# IO_Bottom.net
KiCad netlist of a schematic drawn in EAGLE
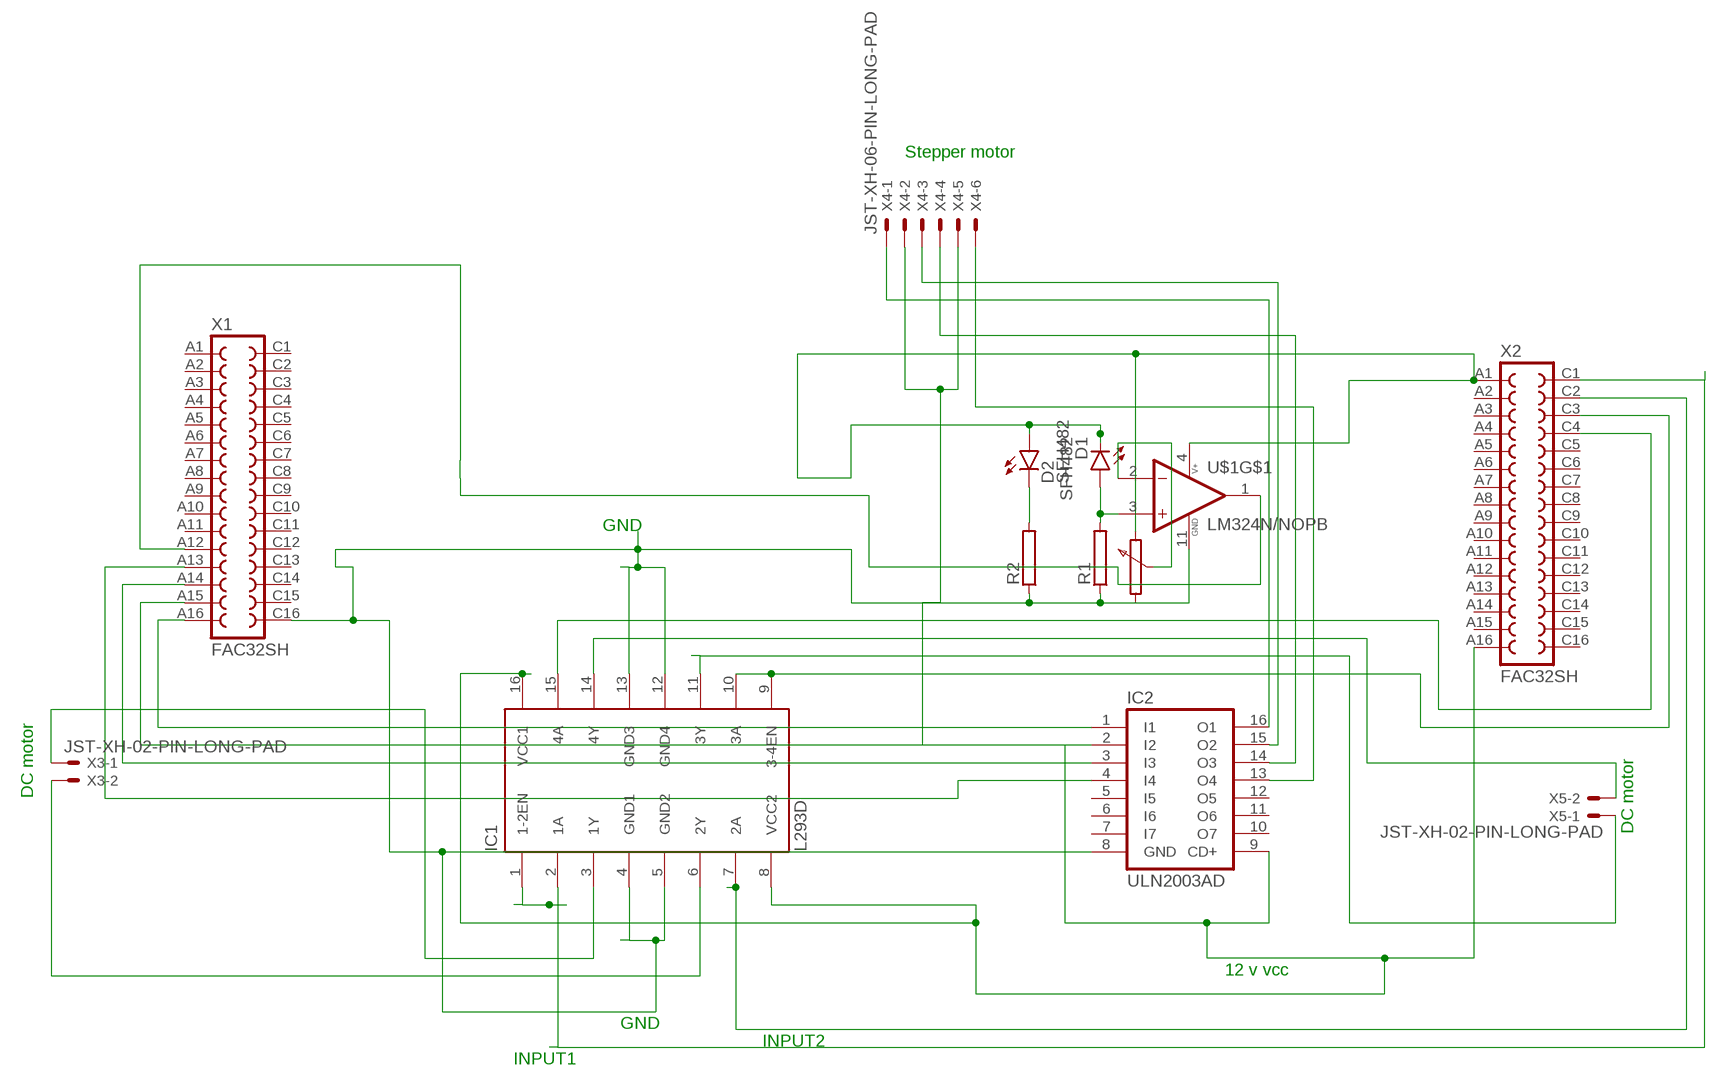
[diagram p0: schematic, sheet 1]

(export (version "E")
  (design (tool "Eeschema 10.0.6"))
  (components
    (comp (ref "D1")
      (value "SFH482")
      (footprint "eagle-import:SFH482")
      (libsource (lib "eagle-import") (part "SFH482"))
    )
    (comp (ref "D2")
      (value "SFH482")
      (footprint "eagle-import:SFH482")
      (libsource (lib "eagle-import") (part "SFH482"))
    )
    (comp (ref "IC1")
      (value "L293D")
      (footprint "eagle-import:DIL16")
      (libsource (lib "eagle-import") (part "L293D"))
    )
    (comp (ref "IC2")
      (value "ULN2003AD")
      (footprint "eagle-import:SO16")
      (libsource (lib "eagle-import") (part "ULN2003AD"))
    )
    (comp (ref "R1")
      (value "RMG100-H")
      (footprint "eagle-import:TO-247-2H")
      (libsource (lib "eagle-import") (part "RMG100-H"))
    )
    (comp (ref "R2")
      (value "RMG100-H")
      (footprint "eagle-import:TO-247-2H")
      (libsource (lib "eagle-import") (part "RMG100-H"))
    )
    (comp (ref "U$1")
      (value "LM324N/NOPB")
      (footprint "eagle-import:DIP825W47P254L1917H533Q14")
      (fields (field (name "MF") "Texas Instruments") (field (name "MP") "LM324N"))
      (libsource (lib "eagle-import") (part "LM324N/NOPB"))
    )
    (comp (ref "X1")
      (value "FAC32SH")
      (footprint "eagle-import:FAC32SH")
      (libsource (lib "eagle-import") (part "FAC32SH"))
    )
    (comp (ref "X2")
      (value "FAC32SH")
      (footprint "eagle-import:FAC32SH")
      (libsource (lib "eagle-import") (part "FAC32SH"))
    )
    (comp (ref "X3")
      (value "JST-XH-02-PIN-LONG-PAD")
      (footprint "eagle-import:JST-XH-02-PACKAGE-LONG-PAD")
      (libsource (lib "eagle-import") (part "JST-XH-02-PIN-LONG-PAD"))
    )
    (comp (ref "X4")
      (value "JST-XH-06-PIN-LONG-PAD")
      (footprint "eagle-import:JST-XH-06-PACKAGE-LONG-PAD")
      (libsource (lib "eagle-import") (part "JST-XH-06-PIN-LONG-PAD"))
    )
    (comp (ref "X5")
      (value "JST-XH-02-PIN-LONG-PAD")
      (footprint "eagle-import:JST-XH-02-PACKAGE-LONG-PAD")
      (libsource (lib "eagle-import") (part "JST-XH-02-PIN-LONG-PAD"))
    )
  )
  (nets
    (net (code "1") (name "Net-(D1-C)") (class "Default")
      (node (ref "D1") (pin "K") (pinfunction "C_K") (pintype "passive"))
      (node (ref "D2") (pin "A") (pinfunction "A_A") (pintype "passive"))
      (node (ref "U$1") (pin "4") (pinfunction "V+_4") (pintype "power_in"))
      (node (ref "X2") (pin "A1") (pinfunction "A1_A1") (pintype "passive"))
    )
    (net (code "2") (name "Net-(D2-C)") (class "Default")
      (node (ref "D2") (pin "K") (pinfunction "C_K") (pintype "passive"))
      (node (ref "R2") (pin "2") (pinfunction "2_2") (pintype "passive"))
    )
    (net (code "3") (name "Net-(IC1-1A)") (class "Default")
      (node (ref "IC1") (pin "2") (pinfunction "1A_2") (pintype "input"))
      (node (ref "X2") (pin "C1") (pinfunction "C1_C1") (pintype "passive"))
    )
    (net (code "4") (name "Net-(IC1-1Y)") (class "Default")
      (node (ref "IC1") (pin "3") (pinfunction "1Y_3") (pintype "output"))
      (node (ref "X3") (pin "1") (pinfunction "S_1") (pintype "passive"))
    )
    (net (code "5") (name "Net-(IC1-2A)") (class "Default")
      (node (ref "IC1") (pin "7") (pinfunction "2A_7") (pintype "input"))
      (node (ref "X2") (pin "C2") (pinfunction "C2_C2") (pintype "passive"))
    )
    (net (code "6") (name "Net-(IC1-2Y)") (class "Default")
      (node (ref "IC1") (pin "6") (pinfunction "2Y_6") (pintype "output"))
      (node (ref "X3") (pin "2") (pinfunction "S_2") (pintype "passive"))
    )
    (net (code "7") (name "Net-(IC1-3-4EN)") (class "Default")
      (node (ref "IC1") (pin "10") (pinfunction "3A_10") (pintype "input"))
      (node (ref "IC1") (pin "9") (pinfunction "3-4EN_9") (pintype "input"))
      (node (ref "X2") (pin "C3") (pinfunction "C3_C3") (pintype "passive"))
    )
    (net (code "8") (name "Net-(IC1-3Y)") (class "Default")
      (node (ref "IC1") (pin "11") (pinfunction "3Y_11") (pintype "output"))
      (node (ref "X5") (pin "1") (pinfunction "S_1") (pintype "passive"))
    )
    (net (code "9") (name "Net-(IC1-4A)") (class "Default")
      (node (ref "IC1") (pin "15") (pinfunction "4A_15") (pintype "input"))
      (node (ref "X2") (pin "C4") (pinfunction "C4_C4") (pintype "passive"))
    )
    (net (code "10") (name "Net-(IC1-4Y)") (class "Default")
      (node (ref "IC1") (pin "14") (pinfunction "4Y_14") (pintype "output"))
      (node (ref "X5") (pin "2") (pinfunction "S_2") (pintype "passive"))
    )
    (net (code "11") (name "Net-(IC1-GND1)") (class "Default")
      (node (ref "IC1") (pin "12") (pinfunction "GND4_12") (pintype "power_in"))
      (node (ref "IC1") (pin "13") (pinfunction "GND3_13") (pintype "power_in"))
      (node (ref "IC1") (pin "4") (pinfunction "GND1_4") (pintype "power_in"))
      (node (ref "IC1") (pin "5") (pinfunction "GND2_5") (pintype "power_in"))
      (node (ref "IC2") (pin "8") (pinfunction "GND_8") (pintype "power_in"))
      (node (ref "R1") (pin "1") (pinfunction "1_1") (pintype "passive"))
      (node (ref "R2") (pin "1") (pinfunction "1_1") (pintype "passive"))
      (node (ref "U$1") (pin "11") (pinfunction "GND_11") (pintype "power_in"))
      (node (ref "X1") (pin "C16") (pinfunction "C16_C16") (pintype "passive"))
    )
    (net (code "12") (name "Net-(IC1-VCC1)") (class "Default")
      (node (ref "IC1") (pin "16") (pinfunction "VCC1_16") (pintype "power_in"))
      (node (ref "IC1") (pin "8") (pinfunction "VCC2_8") (pintype "power_in"))
      (node (ref "IC2") (pin "9") (pinfunction "CD+_9") (pintype "passive"))
      (node (ref "X2") (pin "A16") (pinfunction "A16_A16") (pintype "passive"))
      (node (ref "X4") (pin "2") (pinfunction "S_2") (pintype "passive"))
      (node (ref "X4") (pin "5") (pinfunction "S_5") (pintype "passive"))
    )
    (net (code "13") (name "Net-(IC2-I1)") (class "Default")
      (node (ref "IC2") (pin "1") (pinfunction "I1_1") (pintype "input"))
      (node (ref "X1") (pin "A16") (pinfunction "A16_A16") (pintype "passive"))
    )
    (net (code "14") (name "Net-(IC2-I2)") (class "Default")
      (node (ref "IC2") (pin "2") (pinfunction "I2_2") (pintype "input"))
      (node (ref "X1") (pin "A15") (pinfunction "A15_A15") (pintype "passive"))
    )
    (net (code "15") (name "Net-(IC2-I3)") (class "Default")
      (node (ref "IC2") (pin "3") (pinfunction "I3_3") (pintype "input"))
      (node (ref "X1") (pin "A14") (pinfunction "A14_A14") (pintype "passive"))
    )
    (net (code "16") (name "Net-(IC2-I4)") (class "Default")
      (node (ref "IC2") (pin "4") (pinfunction "I4_4") (pintype "input"))
      (node (ref "X1") (pin "A13") (pinfunction "A13_A13") (pintype "passive"))
    )
    (net (code "17") (name "Net-(IC2-O1)") (class "Default")
      (node (ref "IC2") (pin "16") (pinfunction "O1_16") (pintype "open_collector"))
      (node (ref "X4") (pin "1") (pinfunction "S_1") (pintype "passive"))
    )
    (net (code "18") (name "Net-(IC2-O2)") (class "Default")
      (node (ref "IC2") (pin "15") (pinfunction "O2_15") (pintype "open_collector"))
      (node (ref "X4") (pin "3") (pinfunction "S_3") (pintype "passive"))
    )
    (net (code "19") (name "Net-(IC2-O3)") (class "Default")
      (node (ref "IC2") (pin "14") (pinfunction "O3_14") (pintype "open_collector"))
      (node (ref "X4") (pin "4") (pinfunction "S_4") (pintype "passive"))
    )
    (net (code "20") (name "Net-(IC2-O4)") (class "Default")
      (node (ref "IC2") (pin "13") (pinfunction "O4_13") (pintype "open_collector"))
      (node (ref "X4") (pin "6") (pinfunction "S_6") (pintype "passive"))
    )
    (net (code "21") (name "Net-(U$1A-1IN+)") (class "Default")
      (node (ref "D1") (pin "A") (pinfunction "A_A") (pintype "passive"))
      (node (ref "R1") (pin "2") (pinfunction "2_2") (pintype "passive"))
      (node (ref "U$1") (pin "3") (pinfunction "1IN+_3") (pintype "input"))
    )
    (net (code "22") (name "Net-(U$1A-1OUT)") (class "Default")
      (node (ref "U$1") (pin "1") (pinfunction "1OUT_1") (pintype "output"))
      (node (ref "X1") (pin "A12") (pinfunction "A12_A12") (pintype "passive"))
    )
    (net (code "23") (name "unconnected-(IC1-1-2EN-Pad1)") (class "Default")
      (node (ref "IC1") (pin "1") (pinfunction "1-2EN_1") (pintype "input"))
    )
    (net (code "24") (name "unconnected-(IC2-I5-Pad5)") (class "Default")
      (node (ref "IC2") (pin "5") (pinfunction "I5_5") (pintype "input"))
    )
    (net (code "25") (name "unconnected-(IC2-I6-Pad6)") (class "Default")
      (node (ref "IC2") (pin "6") (pinfunction "I6_6") (pintype "input"))
    )
    (net (code "26") (name "unconnected-(IC2-I7-Pad7)") (class "Default")
      (node (ref "IC2") (pin "7") (pinfunction "I7_7") (pintype "input"))
    )
    (net (code "27") (name "unconnected-(IC2-O5-Pad12)") (class "Default")
      (node (ref "IC2") (pin "12") (pinfunction "O5_12") (pintype "open_collector"))
    )
    (net (code "28") (name "unconnected-(IC2-O6-Pad11)") (class "Default")
      (node (ref "IC2") (pin "11") (pinfunction "O6_11") (pintype "open_collector"))
    )
    (net (code "29") (name "unconnected-(IC2-O7-Pad10)") (class "Default")
      (node (ref "IC2") (pin "10") (pinfunction "O7_10") (pintype "open_collector"))
    )
    (net (code "30") (name "unconnected-(U$1A-1IN--Pad2)") (class "Default")
      (node (ref "U$1") (pin "2") (pinfunction "1IN-_2") (pintype "input"))
    )
    (net (code "31") (name "unconnected-(X1-PadA1)") (class "Default")
      (node (ref "X1") (pin "A1") (pinfunction "A1_A1") (pintype "passive"))
    )
    (net (code "32") (name "unconnected-(X1-PadA2)") (class "Default")
      (node (ref "X1") (pin "A2") (pinfunction "A2_A2") (pintype "passive"))
    )
    (net (code "33") (name "unconnected-(X1-PadA3)") (class "Default")
      (node (ref "X1") (pin "A3") (pinfunction "A3_A3") (pintype "passive"))
    )
    (net (code "34") (name "unconnected-(X1-PadA4)") (class "Default")
      (node (ref "X1") (pin "A4") (pinfunction "A4_A4") (pintype "passive"))
    )
    (net (code "35") (name "unconnected-(X1-PadA5)") (class "Default")
      (node (ref "X1") (pin "A5") (pinfunction "A5_A5") (pintype "passive"))
    )
    (net (code "36") (name "unconnected-(X1-PadA6)") (class "Default")
      (node (ref "X1") (pin "A6") (pinfunction "A6_A6") (pintype "passive"))
    )
    (net (code "37") (name "unconnected-(X1-PadA7)") (class "Default")
      (node (ref "X1") (pin "A7") (pinfunction "A7_A7") (pintype "passive"))
    )
    (net (code "38") (name "unconnected-(X1-PadA8)") (class "Default")
      (node (ref "X1") (pin "A8") (pinfunction "A8_A8") (pintype "passive"))
    )
    (net (code "39") (name "unconnected-(X1-PadA9)") (class "Default")
      (node (ref "X1") (pin "A9") (pinfunction "A9_A9") (pintype "passive"))
    )
    (net (code "40") (name "unconnected-(X1-PadA10)") (class "Default")
      (node (ref "X1") (pin "A10") (pinfunction "A10_A10") (pintype "passive"))
    )
    (net (code "41") (name "unconnected-(X1-PadA11)") (class "Default")
      (node (ref "X1") (pin "A11") (pinfunction "A11_A11") (pintype "passive"))
    )
    (net (code "42") (name "unconnected-(X1-PadC1)") (class "Default")
      (node (ref "X1") (pin "C1") (pinfunction "C1_C1") (pintype "passive"))
    )
    (net (code "43") (name "unconnected-(X1-PadC2)") (class "Default")
      (node (ref "X1") (pin "C2") (pinfunction "C2_C2") (pintype "passive"))
    )
    (net (code "44") (name "unconnected-(X1-PadC3)") (class "Default")
      (node (ref "X1") (pin "C3") (pinfunction "C3_C3") (pintype "passive"))
    )
    (net (code "45") (name "unconnected-(X1-PadC4)") (class "Default")
      (node (ref "X1") (pin "C4") (pinfunction "C4_C4") (pintype "passive"))
    )
    (net (code "46") (name "unconnected-(X1-PadC5)") (class "Default")
      (node (ref "X1") (pin "C5") (pinfunction "C5_C5") (pintype "passive"))
    )
    (net (code "47") (name "unconnected-(X1-PadC6)") (class "Default")
      (node (ref "X1") (pin "C6") (pinfunction "C6_C6") (pintype "passive"))
    )
    (net (code "48") (name "unconnected-(X1-PadC7)") (class "Default")
      (node (ref "X1") (pin "C7") (pinfunction "C7_C7") (pintype "passive"))
    )
    (net (code "49") (name "unconnected-(X1-PadC8)") (class "Default")
      (node (ref "X1") (pin "C8") (pinfunction "C8_C8") (pintype "passive"))
    )
    (net (code "50") (name "unconnected-(X1-PadC9)") (class "Default")
      (node (ref "X1") (pin "C9") (pinfunction "C9_C9") (pintype "passive"))
    )
    (net (code "51") (name "unconnected-(X1-PadC10)") (class "Default")
      (node (ref "X1") (pin "C10") (pinfunction "C10_C10") (pintype "passive"))
    )
    (net (code "52") (name "unconnected-(X1-PadC11)") (class "Default")
      (node (ref "X1") (pin "C11") (pinfunction "C11_C11") (pintype "passive"))
    )
    (net (code "53") (name "unconnected-(X1-PadC12)") (class "Default")
      (node (ref "X1") (pin "C12") (pinfunction "C12_C12") (pintype "passive"))
    )
    (net (code "54") (name "unconnected-(X1-PadC13)") (class "Default")
      (node (ref "X1") (pin "C13") (pinfunction "C13_C13") (pintype "passive"))
    )
    (net (code "55") (name "unconnected-(X1-PadC14)") (class "Default")
      (node (ref "X1") (pin "C14") (pinfunction "C14_C14") (pintype "passive"))
    )
    (net (code "56") (name "unconnected-(X1-PadC15)") (class "Default")
      (node (ref "X1") (pin "C15") (pinfunction "C15_C15") (pintype "passive"))
    )
    (net (code "57") (name "unconnected-(X2-PadA2)") (class "Default")
      (node (ref "X2") (pin "A2") (pinfunction "A2_A2") (pintype "passive"))
    )
    (net (code "58") (name "unconnected-(X2-PadA3)") (class "Default")
      (node (ref "X2") (pin "A3") (pinfunction "A3_A3") (pintype "passive"))
    )
    (net (code "59") (name "unconnected-(X2-PadA4)") (class "Default")
      (node (ref "X2") (pin "A4") (pinfunction "A4_A4") (pintype "passive"))
    )
    (net (code "60") (name "unconnected-(X2-PadA5)") (class "Default")
      (node (ref "X2") (pin "A5") (pinfunction "A5_A5") (pintype "passive"))
    )
    (net (code "61") (name "unconnected-(X2-PadA6)") (class "Default")
      (node (ref "X2") (pin "A6") (pinfunction "A6_A6") (pintype "passive"))
    )
    (net (code "62") (name "unconnected-(X2-PadA7)") (class "Default")
      (node (ref "X2") (pin "A7") (pinfunction "A7_A7") (pintype "passive"))
    )
    (net (code "63") (name "unconnected-(X2-PadA8)") (class "Default")
      (node (ref "X2") (pin "A8") (pinfunction "A8_A8") (pintype "passive"))
    )
    (net (code "64") (name "unconnected-(X2-PadA9)") (class "Default")
      (node (ref "X2") (pin "A9") (pinfunction "A9_A9") (pintype "passive"))
    )
    (net (code "65") (name "unconnected-(X2-PadA10)") (class "Default")
      (node (ref "X2") (pin "A10") (pinfunction "A10_A10") (pintype "passive"))
    )
    (net (code "66") (name "unconnected-(X2-PadA11)") (class "Default")
      (node (ref "X2") (pin "A11") (pinfunction "A11_A11") (pintype "passive"))
    )
    (net (code "67") (name "unconnected-(X2-PadA12)") (class "Default")
      (node (ref "X2") (pin "A12") (pinfunction "A12_A12") (pintype "passive"))
    )
    (net (code "68") (name "unconnected-(X2-PadA13)") (class "Default")
      (node (ref "X2") (pin "A13") (pinfunction "A13_A13") (pintype "passive"))
    )
    (net (code "69") (name "unconnected-(X2-PadA14)") (class "Default")
      (node (ref "X2") (pin "A14") (pinfunction "A14_A14") (pintype "passive"))
    )
    (net (code "70") (name "unconnected-(X2-PadA15)") (class "Default")
      (node (ref "X2") (pin "A15") (pinfunction "A15_A15") (pintype "passive"))
    )
    (net (code "71") (name "unconnected-(X2-PadC5)") (class "Default")
      (node (ref "X2") (pin "C5") (pinfunction "C5_C5") (pintype "passive"))
    )
    (net (code "72") (name "unconnected-(X2-PadC6)") (class "Default")
      (node (ref "X2") (pin "C6") (pinfunction "C6_C6") (pintype "passive"))
    )
    (net (code "73") (name "unconnected-(X2-PadC7)") (class "Default")
      (node (ref "X2") (pin "C7") (pinfunction "C7_C7") (pintype "passive"))
    )
    (net (code "74") (name "unconnected-(X2-PadC8)") (class "Default")
      (node (ref "X2") (pin "C8") (pinfunction "C8_C8") (pintype "passive"))
    )
    (net (code "75") (name "unconnected-(X2-PadC9)") (class "Default")
      (node (ref "X2") (pin "C9") (pinfunction "C9_C9") (pintype "passive"))
    )
    (net (code "76") (name "unconnected-(X2-PadC10)") (class "Default")
      (node (ref "X2") (pin "C10") (pinfunction "C10_C10") (pintype "passive"))
    )
    (net (code "77") (name "unconnected-(X2-PadC11)") (class "Default")
      (node (ref "X2") (pin "C11") (pinfunction "C11_C11") (pintype "passive"))
    )
    (net (code "78") (name "unconnected-(X2-PadC12)") (class "Default")
      (node (ref "X2") (pin "C12") (pinfunction "C12_C12") (pintype "passive"))
    )
    (net (code "79") (name "unconnected-(X2-PadC13)") (class "Default")
      (node (ref "X2") (pin "C13") (pinfunction "C13_C13") (pintype "passive"))
    )
    (net (code "80") (name "unconnected-(X2-PadC14)") (class "Default")
      (node (ref "X2") (pin "C14") (pinfunction "C14_C14") (pintype "passive"))
    )
    (net (code "81") (name "unconnected-(X2-PadC15)") (class "Default")
      (node (ref "X2") (pin "C15") (pinfunction "C15_C15") (pintype "passive"))
    )
    (net (code "82") (name "unconnected-(X2-PadC16)") (class "Default")
      (node (ref "X2") (pin "C16") (pinfunction "C16_C16") (pintype "passive"))
    )
  )
)
